# samd21_actuatorhub_Lite_TQFP32_1_0_feb20.net
KiCad netlist of a schematic drawn in EAGLE
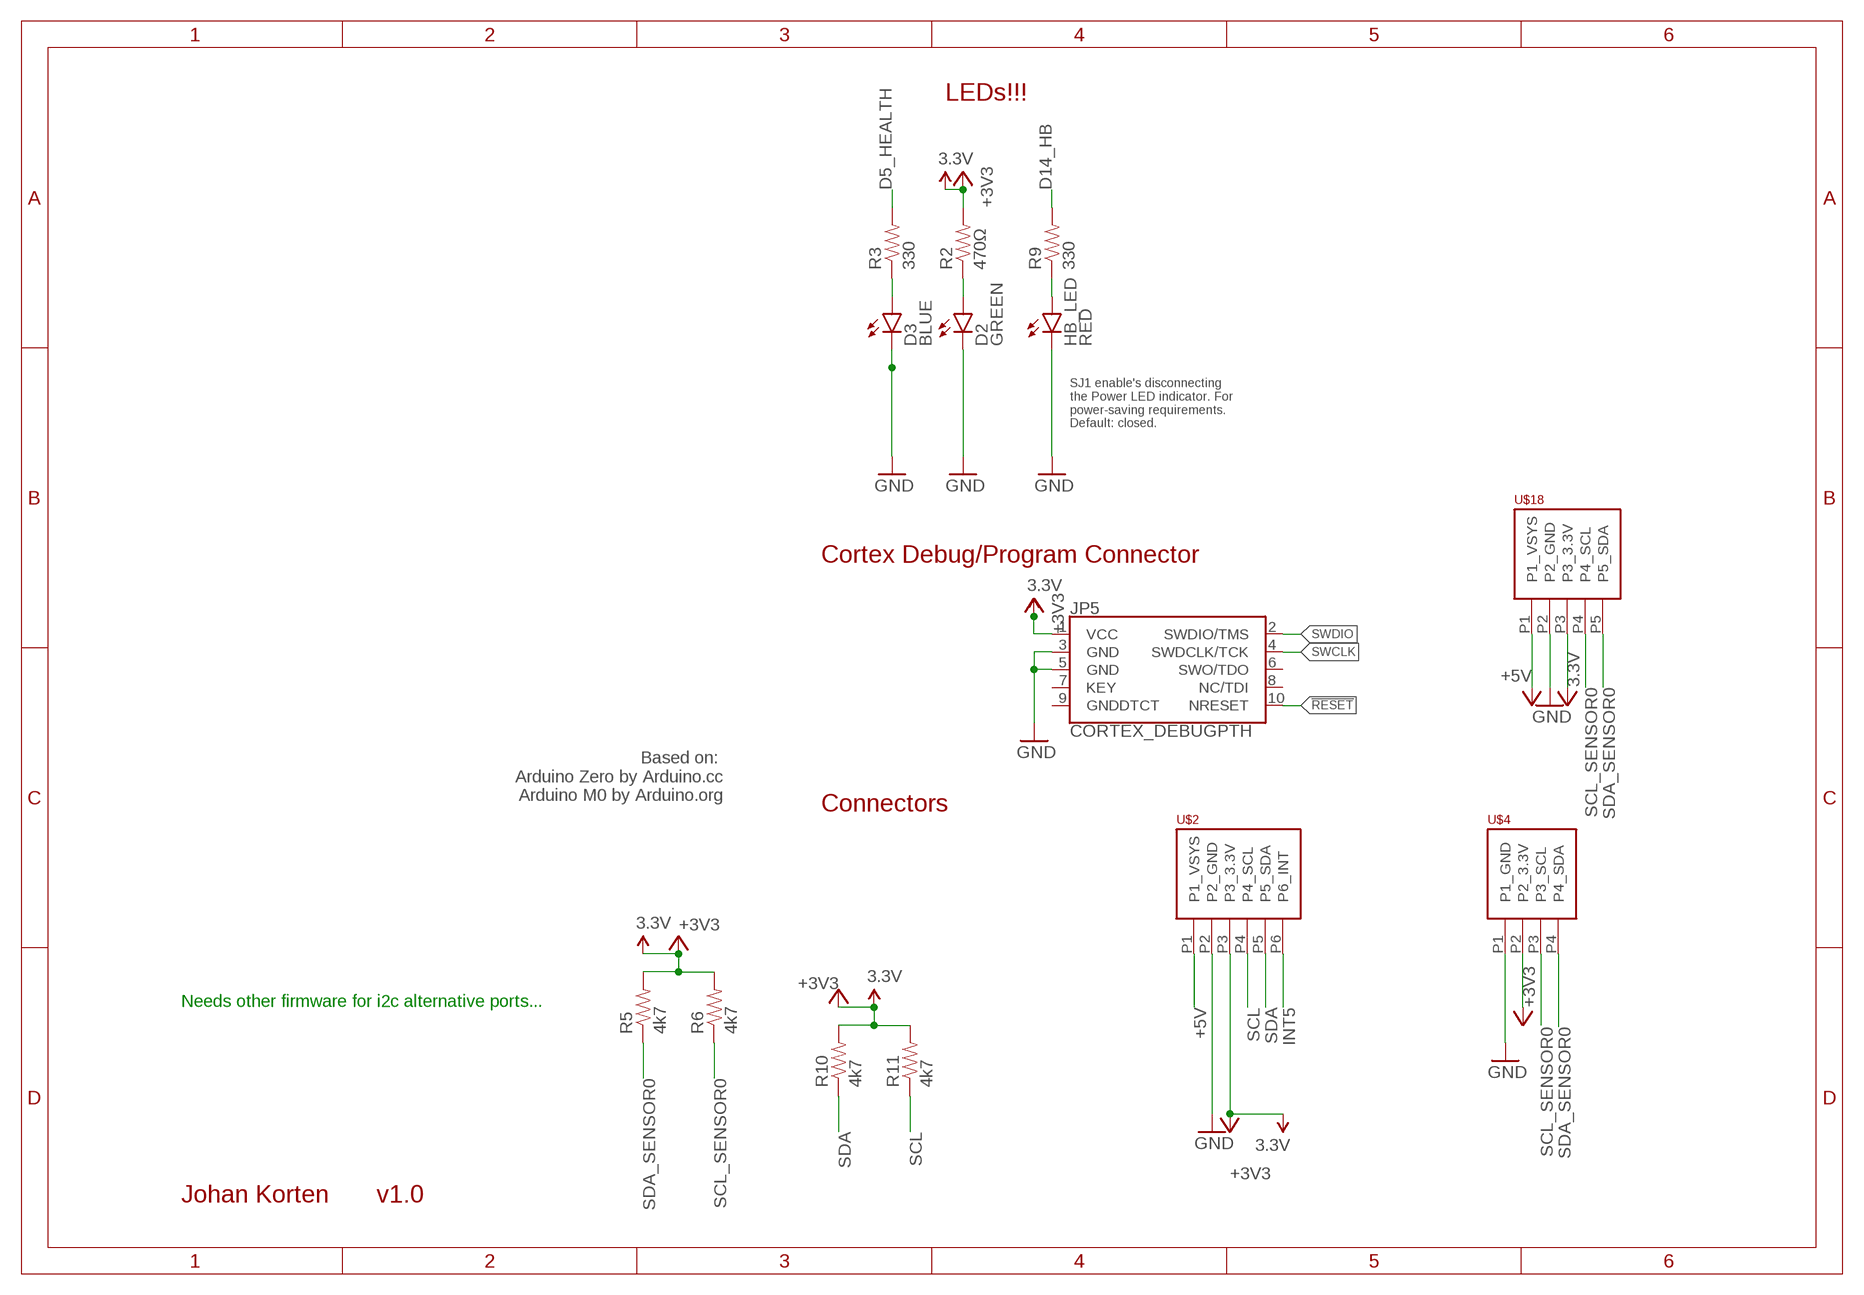
[diagram p0: schematic, sheet 1]
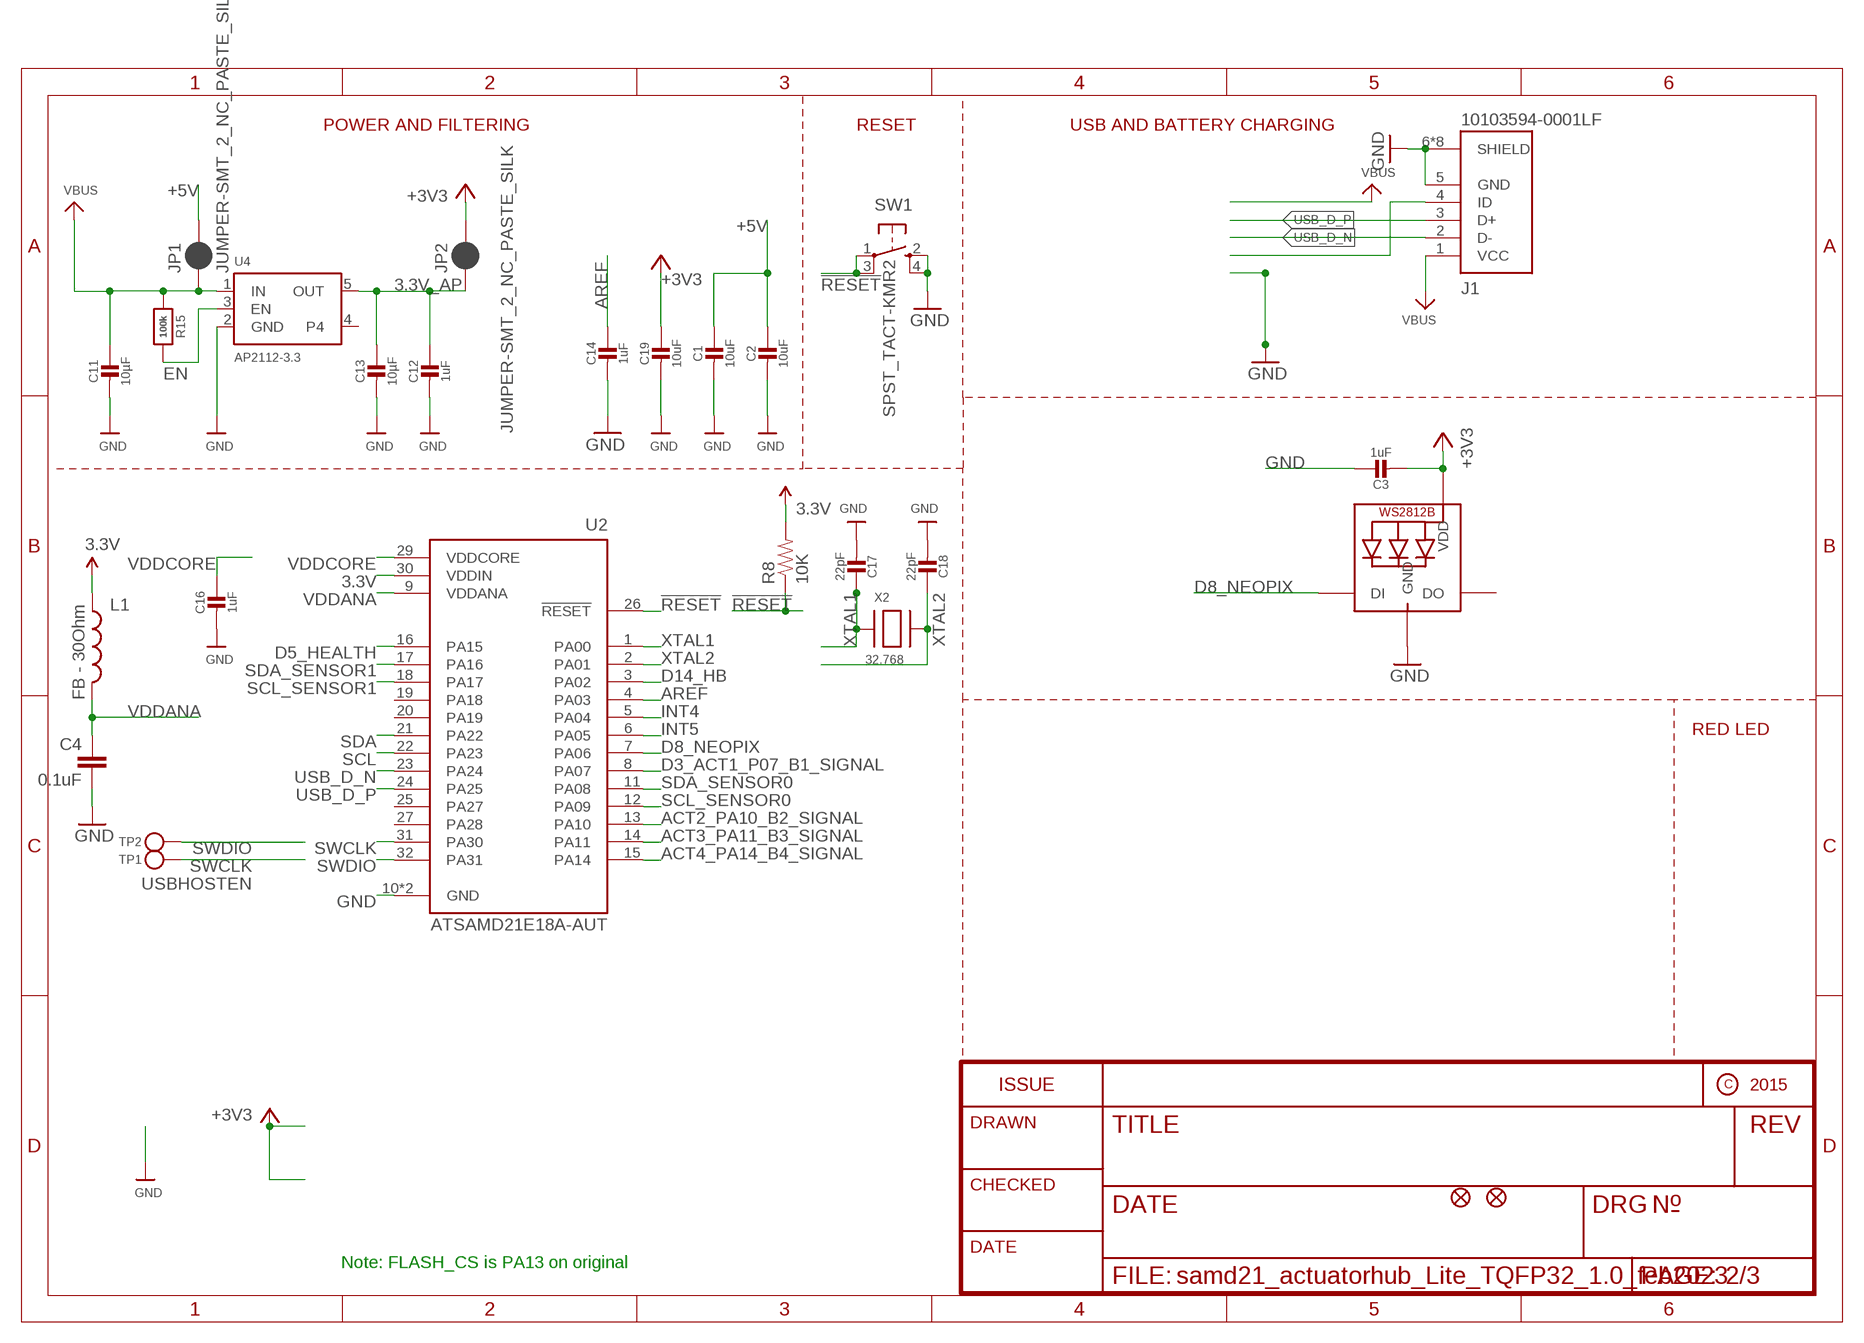
[diagram p1: schematic, sheet 2]
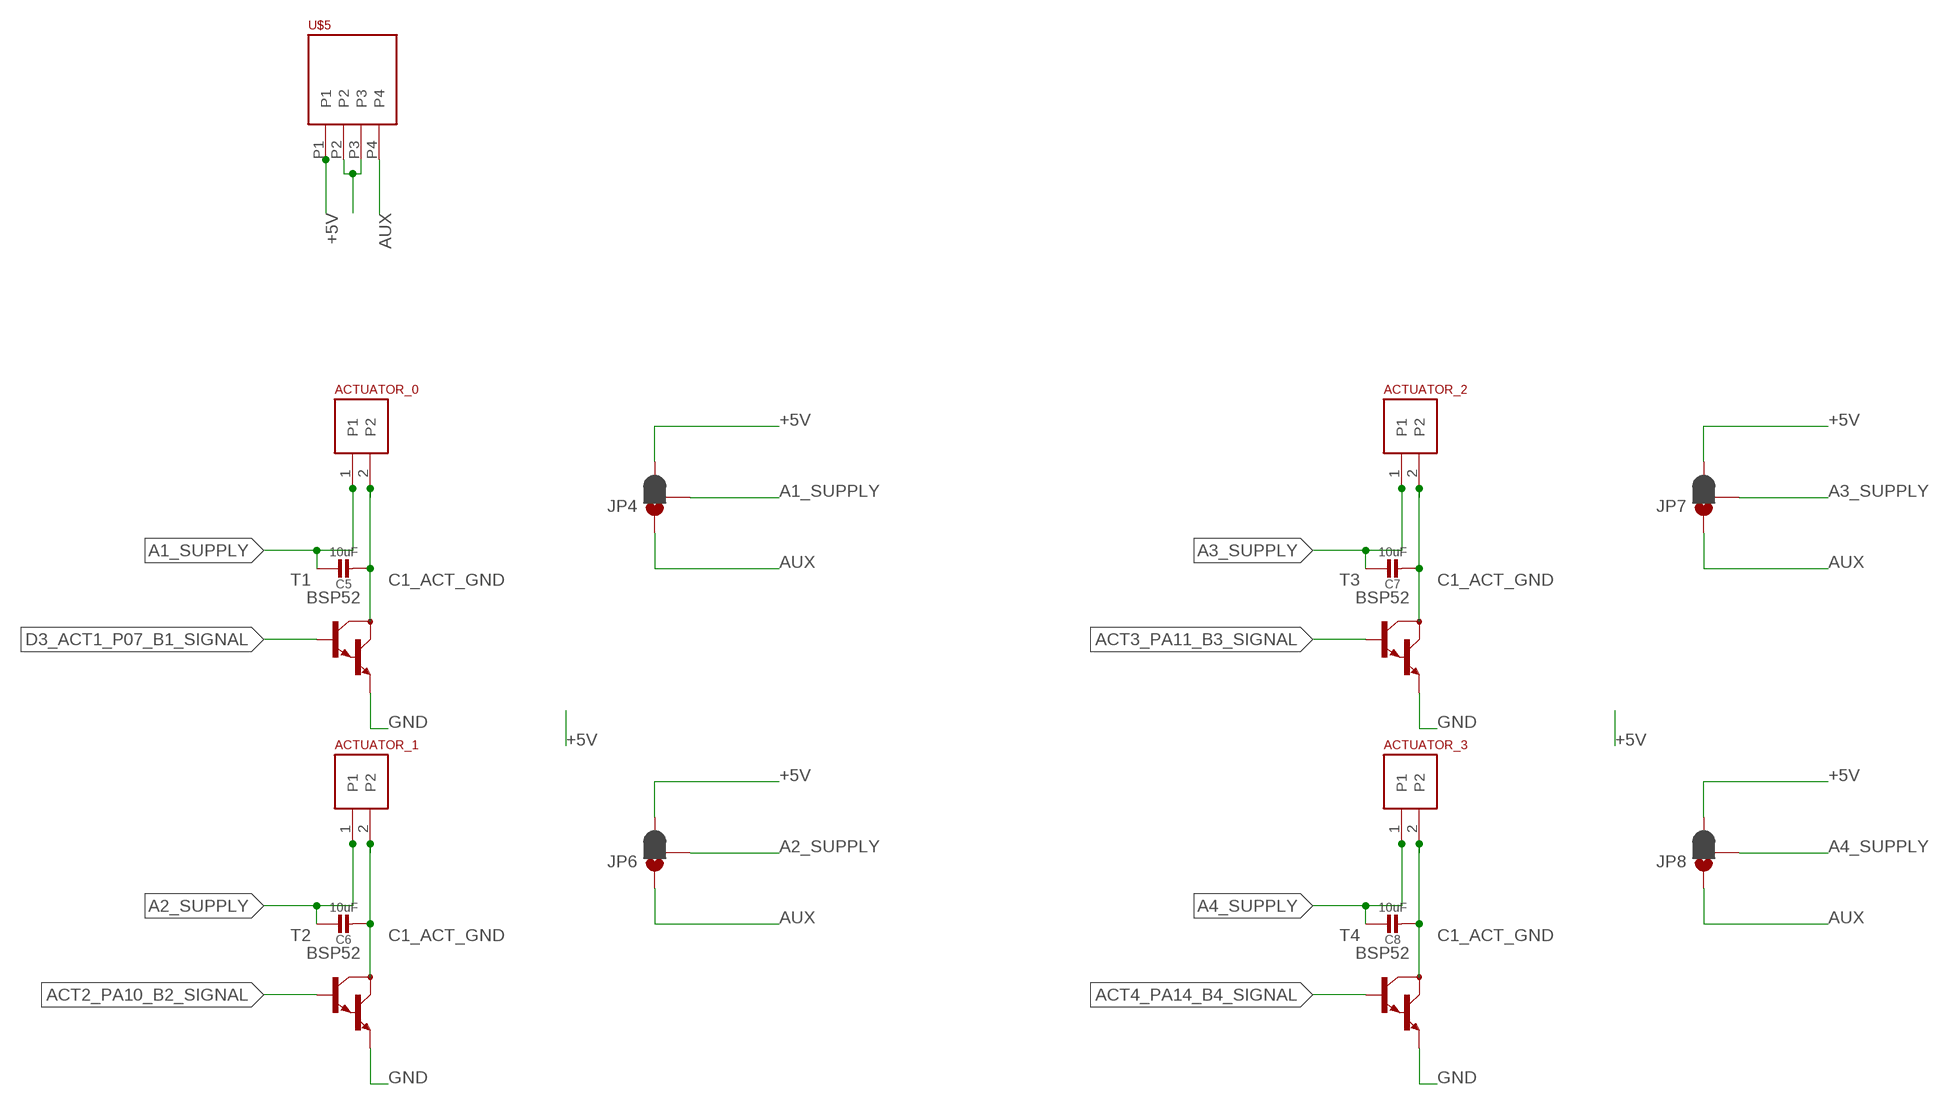
[diagram p2: schematic, sheet 3]

(export (version "E")
  (design (tool "Eeschema 10.0.6"))
  (components
    (comp (ref "C1")
      (value "10uF")
      (footprint "eagle-import:0805-NO")
      (libsource (lib "eagle-import") (part "CAP_CERAMIC0805-NOOUTLINE"))
    )
    (comp (ref "C2")
      (value "10uF")
      (footprint "eagle-import:0805-NO")
      (libsource (lib "eagle-import") (part "CAP_CERAMIC0805-NOOUTLINE"))
    )
    (comp (ref "C3")
      (value "1uF")
      (footprint "eagle-import:0603-NO")
      (libsource (lib "eagle-import") (part "CAP_CERAMIC0603_NO"))
    )
    (comp (ref "C4")
      (value "0.1uF")
      (footprint "eagle-import:0402-CAP")
      (libsource (lib "eagle-import") (part "0.1UF-16V(+-10%)(0402)"))
    )
    (comp (ref "C11")
      (value "10µF")
      (footprint "eagle-import:0805-NO")
      (libsource (lib "eagle-import") (part "CAP_CERAMIC0805-NOOUTLINE"))
    )
    (comp (ref "C12")
      (value "1uF")
      (footprint "eagle-import:0603-NO")
      (libsource (lib "eagle-import") (part "CAP_CERAMIC0603_NO"))
    )
    (comp (ref "C13")
      (value "10µF")
      (footprint "eagle-import:0805-NO")
      (libsource (lib "eagle-import") (part "CAP_CERAMIC0805-NOOUTLINE"))
    )
    (comp (ref "C14")
      (value "1uF")
      (footprint "eagle-import:0603-NO")
      (libsource (lib "eagle-import") (part "CAP_CERAMIC0603_NO"))
    )
    (comp (ref "C16")
      (value "1uF")
      (footprint "eagle-import:0603-NO")
      (libsource (lib "eagle-import") (part "CAP_CERAMIC0603_NO"))
    )
    (comp (ref "C17")
      (value "22pF")
      (footprint "eagle-import:0603-NO")
      (libsource (lib "eagle-import") (part "CAP_CERAMIC0603_NO"))
    )
    (comp (ref "C18")
      (value "22pF")
      (footprint "eagle-import:0603-NO")
      (libsource (lib "eagle-import") (part "CAP_CERAMIC0603_NO"))
    )
    (comp (ref "C19")
      (value "10uF")
      (footprint "eagle-import:0805-NO")
      (libsource (lib "eagle-import") (part "CAP_CERAMIC0805-NOOUTLINE"))
    )
    (comp (ref "J1")
      (value "10103594-0001LF")
      (footprint "eagle-import:AMPHENOL_10103594-0001LF")
      (fields (field (name "MF") "AMPHENOL ICC / FCI"))
      (libsource (lib "eagle-import") (part "10103594-0001LF"))
    )
    (comp (ref "JP1")
      (value "JUMPER-SMT_2_NC_PASTE_SILK")
      (footprint "eagle-import:SMT-JUMPER_2_NC_PASTE_SILK")
      (libsource (lib "eagle-import") (part "JUMPER-SMT_2_NC_PASTE_SILK"))
    )
    (comp (ref "JP2")
      (value "JUMPER-SMT_2_NC_PASTE_SILK")
      (footprint "eagle-import:SMT-JUMPER_2_NC_PASTE_SILK")
      (libsource (lib "eagle-import") (part "JUMPER-SMT_2_NC_PASTE_SILK"))
    )
    (comp (ref "L1")
      (value "FB - 30Ohm")
      (footprint "eagle-import:0603")
      (libsource (lib "eagle-import") (part "INDUCTOR0603"))
    )
    (comp (ref "LED1")
      (value "WS2812B3535")
      (footprint "eagle-import:LED3535")
      (libsource (lib "eagle-import") (part "WS2812B3535"))
    )
    (comp (ref "R8")
      (value "10K")
      (footprint "eagle-import:0603-RES")
      (libsource (lib "eagle-import") (part "10KOHM-1/10W-1%(0603)0603"))
    )
    (comp (ref "R15")
      (value "100k")
      (footprint "eagle-import:0603-NO")
      (libsource (lib "eagle-import") (part "RESISTOR_0603_NOOUT"))
    )
    (comp (ref "SW1")
      (value "SPST_TACT-KMR2")
      (footprint "eagle-import:KMR2")
      (libsource (lib "eagle-import") (part "SPST_TACT-KMR2"))
    )
    (comp (ref "TP1")
      (value "TESTPOINTROUND1.5MM")
      (footprint "eagle-import:TESTPOINT_ROUND_1.5MM")
      (libsource (lib "eagle-import") (part "TESTPOINTROUND1.5MM"))
    )
    (comp (ref "TP2")
      (value "TESTPOINTROUND1.5MM")
      (footprint "eagle-import:TESTPOINT_ROUND_1.5MM")
      (libsource (lib "eagle-import") (part "TESTPOINTROUND1.5MM"))
    )
    (comp (ref "U$34")
      (value "FIDUCIAL\"\"")
      (footprint "eagle-import:FIDUCIAL_1MM")
      (libsource (lib "eagle-import") (part "FIDUCIAL{dblquote}{dblquote}"))
    )
    (comp (ref "U$35")
      (value "FIDUCIAL\"\"")
      (footprint "eagle-import:FIDUCIAL_1MM")
      (libsource (lib "eagle-import") (part "FIDUCIAL{dblquote}{dblquote}"))
    )
    (comp (ref "U2")
      (value "ATSAMD21E18A-AUT")
      (footprint "eagle-import:QFP80P900X900X120-32N")
      (fields (field (name "MF") "Microchip") (field (name "MP") "ATSAMD21E18A-AU"))
      (libsource (lib "eagle-import") (part "ATSAMD21E18A-AUT"))
    )
    (comp (ref "U4")
      (value "AP2112-3.3")
      (footprint "eagle-import:SOT23-5")
      (libsource (lib "eagle-import") (part "VREG_SOT23-5"))
    )
    (comp (ref "X2")
      (value "32.768")
      (footprint "eagle-import:XTAL3215")
      (libsource (lib "eagle-import") (part "XTAL-3.2X1.5"))
    )
    (comp (ref "ACTUATOR_0")
      (value "PHOENIX_PTSM_M2TH")
      (footprint "eagle-import:PTSM_M2_THRHOLE")
      (libsource (lib "eagle-import") (part "PHOENIX_PTSM_M2TH"))
    )
    (comp (ref "ACTUATOR_1")
      (value "PHOENIX_PTSM_M2TH")
      (footprint "eagle-import:PTSM_M2_THRHOLE")
      (libsource (lib "eagle-import") (part "PHOENIX_PTSM_M2TH"))
    )
    (comp (ref "ACTUATOR_2")
      (value "PHOENIX_PTSM_M2TH")
      (footprint "eagle-import:PTSM_M2_THRHOLE")
      (libsource (lib "eagle-import") (part "PHOENIX_PTSM_M2TH"))
    )
    (comp (ref "ACTUATOR_3")
      (value "PHOENIX_PTSM_M2TH")
      (footprint "eagle-import:PTSM_M2_THRHOLE")
      (libsource (lib "eagle-import") (part "PHOENIX_PTSM_M2TH"))
    )
    (comp (ref "C5")
      (value "10uF")
      (footprint "eagle-import:0805-NO")
      (libsource (lib "eagle-import") (part "CAP_CERAMIC0805-NOOUTLINE"))
    )
    (comp (ref "C6")
      (value "10uF")
      (footprint "eagle-import:0805-NO")
      (libsource (lib "eagle-import") (part "CAP_CERAMIC0805-NOOUTLINE"))
    )
    (comp (ref "C7")
      (value "10uF")
      (footprint "eagle-import:0805-NO")
      (libsource (lib "eagle-import") (part "CAP_CERAMIC0805-NOOUTLINE"))
    )
    (comp (ref "C8")
      (value "10uF")
      (footprint "eagle-import:0805-NO")
      (libsource (lib "eagle-import") (part "CAP_CERAMIC0805-NOOUTLINE"))
    )
    (comp (ref "JP4")
      (value "JUMPER-SMT_3_1-NC_PASTE_SILK")
      (footprint "eagle-import:SMT-JUMPER_3_1-NC_PASTE_SILK")
      (libsource (lib "eagle-import") (part "JUMPER-SMT_3_1-NC_PASTE_SILK"))
    )
    (comp (ref "JP6")
      (value "JUMPER-SMT_3_1-NC_PASTE_SILK")
      (footprint "eagle-import:SMT-JUMPER_3_1-NC_PASTE_SILK")
      (libsource (lib "eagle-import") (part "JUMPER-SMT_3_1-NC_PASTE_SILK"))
    )
    (comp (ref "JP7")
      (value "JUMPER-SMT_3_1-NC_PASTE_SILK")
      (footprint "eagle-import:SMT-JUMPER_3_1-NC_PASTE_SILK")
      (libsource (lib "eagle-import") (part "JUMPER-SMT_3_1-NC_PASTE_SILK"))
    )
    (comp (ref "JP8")
      (value "JUMPER-SMT_3_1-NC_PASTE_SILK")
      (footprint "eagle-import:SMT-JUMPER_3_1-NC_PASTE_SILK")
      (libsource (lib "eagle-import") (part "JUMPER-SMT_3_1-NC_PASTE_SILK"))
    )
    (comp (ref "T1")
      (value "BSP52")
      (footprint "eagle-import:SOT-223-4")
      (fields (field (name "MF") "ON Semiconductor"))
      (libsource (lib "eagle-import") (part "BSP52"))
    )
    (comp (ref "T2")
      (value "BSP52")
      (footprint "eagle-import:SOT-223-4")
      (fields (field (name "MF") "ON Semiconductor"))
      (libsource (lib "eagle-import") (part "BSP52"))
    )
    (comp (ref "T3")
      (value "BSP52")
      (footprint "eagle-import:SOT-223-4")
      (fields (field (name "MF") "ON Semiconductor"))
      (libsource (lib "eagle-import") (part "BSP52"))
    )
    (comp (ref "T4")
      (value "BSP52")
      (footprint "eagle-import:SOT-223-4")
      (fields (field (name "MF") "ON Semiconductor"))
      (libsource (lib "eagle-import") (part "BSP52"))
    )
    (comp (ref "U$5")
      (value "PHOENIX_PTSM_M4_TH_ANGLE")
      (footprint "eagle-import:PTSM_M4_TH_ANGLE_NEUTRAL")
      (libsource (lib "eagle-import") (part "PHOENIX_PTSM_M4_TH_ANGLE"))
    )
    (comp (ref "D2")
      (value "GREEN")
      (footprint "eagle-import:LED-0603")
      (libsource (lib "eagle-import") (part "LED-RED0603"))
    )
    (comp (ref "D3")
      (value "BLUE")
      (footprint "eagle-import:LED-0603")
      (libsource (lib "eagle-import") (part "LED-BLUE0603"))
    )
    (comp (ref "HB_LED")
      (value "RED")
      (footprint "eagle-import:LED-0603")
      (libsource (lib "eagle-import") (part "LED-RED0603"))
    )
    (comp (ref "JP5")
      (value "CORTEX_DEBUGPTH")
      (footprint "eagle-import:2X5-PTH-1.27MM")
      (libsource (lib "eagle-import") (part "CORTEX_DEBUGPTH"))
    )
    (comp (ref "R2")
      (value "470Ω")
      (footprint "eagle-import:0603-RES")
      (libsource (lib "eagle-import") (part "330OHM1/10W1%(0603)"))
    )
    (comp (ref "R3")
      (value "330")
      (footprint "eagle-import:0603-RES")
      (libsource (lib "eagle-import") (part "330OHM1/10W1%(0603)"))
    )
    (comp (ref "R5")
      (value "4k7")
      (footprint "eagle-import:0603-RES")
      (libsource (lib "eagle-import") (part "330OHM1/10W1%(0603)"))
    )
    (comp (ref "R6")
      (value "4k7")
      (footprint "eagle-import:0603-RES")
      (libsource (lib "eagle-import") (part "330OHM1/10W1%(0603)"))
    )
    (comp (ref "R9")
      (value "330")
      (footprint "eagle-import:0603-RES")
      (libsource (lib "eagle-import") (part "330OHM1/10W1%(0603)"))
    )
    (comp (ref "R10")
      (value "4k7")
      (footprint "eagle-import:0603-RES")
      (libsource (lib "eagle-import") (part "330OHM1/10W1%(0603)"))
    )
    (comp (ref "R11")
      (value "4k7")
      (footprint "eagle-import:0603-RES")
      (libsource (lib "eagle-import") (part "330OHM1/10W1%(0603)"))
    )
    (comp (ref "U$2")
      (value "PHOENIX_PTSM_M6_TH_I2CPPANGLE")
      (footprint "eagle-import:PTSM_M6_THRHOLE")
      (libsource (lib "eagle-import") (part "PHOENIX_PTSM_M6_TH_I2CPPANGLE"))
    )
    (comp (ref "U$4")
      (value "PHOENIX_PTSM_M4_THANGLE")
      (footprint "eagle-import:PTSM_M4_TH")
      (libsource (lib "eagle-import") (part "PHOENIX_PTSM_M4_THANGLE"))
    )
    (comp (ref "U$18")
      (value "PHOENIX_PTSM_M5_TH_I2C++")
      (footprint "eagle-import:PTSM_M5_THRHOLE")
      (libsource (lib "eagle-import") (part "PHOENIX_PTSM_M5_TH_I2C++"))
    )
  )
  (nets
    (net (code "1") (name "+5V") (class "Default")
      (node (ref "C1") (pin "1") (pinfunction "1_1") (pintype "passive"))
      (node (ref "C2") (pin "1") (pinfunction "1_1") (pintype "passive"))
      (node (ref "JP1") (pin "2") (pinfunction "2_2") (pintype "passive"))
      (node (ref "JP4") (pin "3") (pinfunction "3_3") (pintype "passive"))
      (node (ref "JP6") (pin "3") (pinfunction "3_3") (pintype "passive"))
      (node (ref "JP7") (pin "3") (pinfunction "3_3") (pintype "passive"))
      (node (ref "JP8") (pin "3") (pinfunction "3_3") (pintype "passive"))
      (node (ref "U$18") (pin "P1") (pinfunction "P1_VSYS_P1") (pintype "power_in"))
      (node (ref "U$2") (pin "P1") (pinfunction "P1_VSYS_P1") (pintype "power_in"))
      (node (ref "U$5") (pin "P1") (pinfunction "P1_P1") (pintype "power_in"))
    )
    (net (code "2") (name "3.3V") (class "Default")
      (node (ref "C19") (pin "1") (pinfunction "1_1") (pintype "passive"))
      (node (ref "C3") (pin "2") (pinfunction "2_2") (pintype "passive"))
      (node (ref "JP2") (pin "2") (pinfunction "2_2") (pintype "passive"))
      (node (ref "JP5") (pin "1") (pinfunction "VCC_1") (pintype "bidirectional"))
      (node (ref "L1") (pin "1") (pinfunction "1_1") (pintype "passive"))
      (node (ref "LED1") (pin "2") (pinfunction "VDD_2") (pintype "power_in"))
      (node (ref "R10") (pin "2") (pinfunction "2_2") (pintype "passive"))
      (node (ref "R11") (pin "2") (pinfunction "2_2") (pintype "passive"))
      (node (ref "R2") (pin "2") (pinfunction "2_2") (pintype "passive"))
      (node (ref "R5") (pin "2") (pinfunction "2_2") (pintype "passive"))
      (node (ref "R6") (pin "2") (pinfunction "2_2") (pintype "passive"))
      (node (ref "R8") (pin "2") (pinfunction "2_2") (pintype "passive"))
      (node (ref "U$18") (pin "P3") (pinfunction "P3_3.3V_P3") (pintype "power_in"))
      (node (ref "U$2") (pin "P3") (pinfunction "P3_3.3V_P3") (pintype "power_in"))
      (node (ref "U$4") (pin "P2") (pinfunction "P2_3.3V_P2") (pintype "power_in"))
      (node (ref "U2") (pin "30") (pinfunction "VDDIN_30") (pintype "power_in"))
    )
    (net (code "3") (name "3.3V_AP") (class "Default")
      (node (ref "C12") (pin "1") (pinfunction "1_1") (pintype "passive"))
      (node (ref "C13") (pin "1") (pinfunction "1_1") (pintype "passive"))
      (node (ref "JP2") (pin "1") (pinfunction "1_1") (pintype "passive"))
      (node (ref "U4") (pin "5") (pinfunction "OUT_5") (pintype "power_in"))
    )
    (net (code "4") (name "A1_SUPPLY") (class "Default")
      (node (ref "ACTUATOR_0") (pin "1") (pinfunction "P1_1") (pintype "bidirectional"))
      (node (ref "C5") (pin "1") (pinfunction "1_1") (pintype "passive"))
      (node (ref "JP4") (pin "2") (pinfunction "2_2") (pintype "passive"))
    )
    (net (code "5") (name "A2_SUPPLY") (class "Default")
      (node (ref "ACTUATOR_1") (pin "1") (pinfunction "P1_1") (pintype "bidirectional"))
      (node (ref "C6") (pin "1") (pinfunction "1_1") (pintype "passive"))
      (node (ref "JP6") (pin "2") (pinfunction "2_2") (pintype "passive"))
    )
    (net (code "6") (name "A3_SUPPLY") (class "Default")
      (node (ref "ACTUATOR_2") (pin "1") (pinfunction "P1_1") (pintype "bidirectional"))
      (node (ref "C7") (pin "1") (pinfunction "1_1") (pintype "passive"))
      (node (ref "JP7") (pin "2") (pinfunction "2_2") (pintype "passive"))
    )
    (net (code "7") (name "A4_SUPPLY") (class "Default")
      (node (ref "ACTUATOR_3") (pin "1") (pinfunction "P1_1") (pintype "bidirectional"))
      (node (ref "C8") (pin "1") (pinfunction "1_1") (pintype "passive"))
      (node (ref "JP8") (pin "2") (pinfunction "2_2") (pintype "passive"))
    )
    (net (code "8") (name "ACT2_PA10_B2_SIGNAL") (class "Default")
      (node (ref "T2") (pin "1") (pinfunction "B_1") (pintype "passive"))
      (node (ref "U2") (pin "13") (pinfunction "PA10_13") (pintype "bidirectional"))
    )
    (net (code "9") (name "ACT3_PA11_B3_SIGNAL") (class "Default")
      (node (ref "T3") (pin "1") (pinfunction "B_1") (pintype "passive"))
      (node (ref "U2") (pin "14") (pinfunction "PA11_14") (pintype "bidirectional"))
    )
    (net (code "10") (name "ACT4_PA14_B4_SIGNAL") (class "Default")
      (node (ref "T4") (pin "1") (pinfunction "B_1") (pintype "passive"))
      (node (ref "U2") (pin "15") (pinfunction "PA14_15") (pintype "bidirectional"))
    )
    (net (code "11") (name "AREF") (class "Default")
      (node (ref "C14") (pin "1") (pinfunction "1_1") (pintype "passive"))
      (node (ref "U2") (pin "4") (pinfunction "PA03_4") (pintype "bidirectional"))
    )
    (net (code "12") (name "AUX") (class "Default")
      (node (ref "JP4") (pin "1") (pinfunction "1_1") (pintype "passive"))
      (node (ref "JP6") (pin "1") (pinfunction "1_1") (pintype "passive"))
      (node (ref "JP7") (pin "1") (pinfunction "1_1") (pintype "passive"))
      (node (ref "JP8") (pin "1") (pinfunction "1_1") (pintype "passive"))
      (node (ref "U$5") (pin "P4") (pinfunction "P4_P4") (pintype "power_in"))
    )
    (net (code "13") (name "C1_ACT_GND") (class "Default")
      (node (ref "ACTUATOR_0") (pin "2") (pinfunction "P2_2") (pintype "bidirectional"))
      (node (ref "ACTUATOR_1") (pin "2") (pinfunction "P2_2") (pintype "bidirectional"))
      (node (ref "ACTUATOR_2") (pin "2") (pinfunction "P2_2") (pintype "bidirectional"))
      (node (ref "ACTUATOR_3") (pin "2") (pinfunction "P2_2") (pintype "bidirectional"))
      (node (ref "C5") (pin "2") (pinfunction "2_2") (pintype "passive"))
      (node (ref "C6") (pin "2") (pinfunction "2_2") (pintype "passive"))
      (node (ref "C7") (pin "2") (pinfunction "2_2") (pintype "passive"))
      (node (ref "C8") (pin "2") (pinfunction "2_2") (pintype "passive"))
      (node (ref "T1") (pin "2") (pinfunction "C_2") (pintype "passive"))
      (node (ref "T1") (pin "4") (pinfunction "C_4") (pintype "passive"))
      (node (ref "T2") (pin "2") (pinfunction "C_2") (pintype "passive"))
      (node (ref "T2") (pin "4") (pinfunction "C_4") (pintype "passive"))
      (node (ref "T3") (pin "2") (pinfunction "C_2") (pintype "passive"))
      (node (ref "T3") (pin "4") (pinfunction "C_4") (pintype "passive"))
      (node (ref "T4") (pin "2") (pinfunction "C_2") (pintype "passive"))
      (node (ref "T4") (pin "4") (pinfunction "C_4") (pintype "passive"))
    )
    (net (code "14") (name "D3_ACT1_P07_B1_SIGNAL") (class "Default")
      (node (ref "T1") (pin "1") (pinfunction "B_1") (pintype "passive"))
      (node (ref "U2") (pin "8") (pinfunction "PA07_8") (pintype "bidirectional"))
    )
    (net (code "15") (name "D5_HEALTH") (class "Default")
      (node (ref "R3") (pin "2") (pinfunction "2_2") (pintype "passive"))
      (node (ref "U2") (pin "16") (pinfunction "PA15_16") (pintype "bidirectional"))
    )
    (net (code "16") (name "D8_NEOPIX") (class "Default")
      (node (ref "LED1") (pin "1") (pinfunction "DI_1") (pintype "input"))
      (node (ref "U2") (pin "7") (pinfunction "PA06_7") (pintype "bidirectional"))
    )
    (net (code "17") (name "D14_HB") (class "Default")
      (node (ref "R9") (pin "2") (pinfunction "2_2") (pintype "passive"))
      (node (ref "U2") (pin "3") (pinfunction "PA02_3") (pintype "bidirectional"))
    )
    (net (code "18") (name "EN") (class "Default")
      (node (ref "R15") (pin "2") (pinfunction "2_2") (pintype "passive"))
      (node (ref "U4") (pin "3") (pinfunction "EN_3") (pintype "input"))
    )
    (net (code "19") (name "GND") (class "Default")
      (node (ref "C1") (pin "2") (pinfunction "2_2") (pintype "passive"))
      (node (ref "C11") (pin "2") (pinfunction "2_2") (pintype "passive"))
      (node (ref "C12") (pin "2") (pinfunction "2_2") (pintype "passive"))
      (node (ref "C13") (pin "2") (pinfunction "2_2") (pintype "passive"))
      (node (ref "C14") (pin "2") (pinfunction "2_2") (pintype "passive"))
      (node (ref "C16") (pin "2") (pinfunction "2_2") (pintype "passive"))
      (node (ref "C17") (pin "2") (pinfunction "2_2") (pintype "passive"))
      (node (ref "C18") (pin "2") (pinfunction "2_2") (pintype "passive"))
      (node (ref "C19") (pin "2") (pinfunction "2_2") (pintype "passive"))
      (node (ref "C2") (pin "2") (pinfunction "2_2") (pintype "passive"))
      (node (ref "C3") (pin "1") (pinfunction "1_1") (pintype "passive"))
      (node (ref "C4") (pin "2") (pinfunction "2_2") (pintype "passive"))
      (node (ref "D2") (pin "C") (pinfunction "C_C") (pintype "passive"))
      (node (ref "D3") (pin "C") (pinfunction "C_C") (pintype "passive"))
      (node (ref "HB_LED") (pin "C") (pinfunction "C_C") (pintype "passive"))
      (node (ref "J1") (pin "10") (pinfunction "SHIELD_10") (pintype "passive"))
      (node (ref "J1") (pin "11") (pinfunction "SHIELD_11") (pintype "passive"))
      (node (ref "J1") (pin "5") (pinfunction "GND_5") (pintype "power_in"))
      (node (ref "J1") (pin "6") (pinfunction "SHIELD_6") (pintype "passive"))
      (node (ref "J1") (pin "7") (pinfunction "SHIELD_7") (pintype "passive"))
      (node (ref "J1") (pin "8") (pinfunction "SHIELD_8") (pintype "passive"))
      (node (ref "J1") (pin "9") (pinfunction "SHIELD_9") (pintype "passive"))
      (node (ref "J1") (pin "S1") (pinfunction "SHIELD_S1") (pintype "passive"))
      (node (ref "J1") (pin "S2") (pinfunction "SHIELD_S2") (pintype "passive"))
      (node (ref "JP5") (pin "3") (pinfunction "GND_3") (pintype "bidirectional"))
      (node (ref "JP5") (pin "5") (pinfunction "GND_5") (pintype "bidirectional"))
      (node (ref "LED1") (pin "4") (pinfunction "GND_4") (pintype "power_in"))
      (node (ref "SW1") (pin "2") (pinfunction "S_2") (pintype "passive"))
      (node (ref "SW1") (pin "4") (pinfunction "S1_4") (pintype "passive"))
      (node (ref "T1") (pin "3") (pinfunction "E_3") (pintype "passive"))
      (node (ref "T2") (pin "3") (pinfunction "E_3") (pintype "passive"))
      (node (ref "T3") (pin "3") (pinfunction "E_3") (pintype "passive"))
      (node (ref "T4") (pin "3") (pinfunction "E_3") (pintype "passive"))
      (node (ref "U$18") (pin "P2") (pinfunction "P2_GND_P2") (pintype "power_in"))
      (node (ref "U$2") (pin "P2") (pinfunction "P2_GND_P2") (pintype "power_in"))
      (node (ref "U$4") (pin "P1") (pinfunction "P1_GND_P1") (pintype "power_in"))
      (node (ref "U2") (pin "10") (pinfunction "GND_10") (pintype "power_in"))
      (node (ref "U2") (pin "28") (pinfunction "GND_28") (pintype "power_in"))
      (node (ref "U4") (pin "2") (pinfunction "GND_2") (pintype "power_in"))
    )
    (net (code "20") (name "INT4") (class "Default")
      (node (ref "U2") (pin "5") (pinfunction "PA04_5") (pintype "bidirectional"))
    )
    (net (code "21") (name "INT5") (class "Default")
      (node (ref "U$2") (pin "P6") (pinfunction "P6_INT_P6") (pintype "power_in"))
      (node (ref "U2") (pin "6") (pinfunction "PA05_6") (pintype "bidirectional"))
    )
    (net (code "22") (name "Net-(D2-PadA)") (class "Default")
      (node (ref "D2") (pin "A") (pinfunction "A_A") (pintype "passive"))
      (node (ref "R2") (pin "1") (pinfunction "1_1") (pintype "passive"))
    )
    (net (code "23") (name "Net-(D3-PadA)") (class "Default")
      (node (ref "D3") (pin "A") (pinfunction "A_A") (pintype "passive"))
      (node (ref "R3") (pin "1") (pinfunction "1_1") (pintype "passive"))
    )
    (net (code "24") (name "Net-(HB_LED-PadA)") (class "Default")
      (node (ref "HB_LED") (pin "A") (pinfunction "A_A") (pintype "passive"))
      (node (ref "R9") (pin "1") (pinfunction "1_1") (pintype "passive"))
    )
    (net (code "25") (name "Net-(U$5-PadP2)") (class "Default")
      (node (ref "U$5") (pin "P2") (pinfunction "P2_P2") (pintype "power_in"))
      (node (ref "U$5") (pin "P3") (pinfunction "P3_P3") (pintype "power_in"))
    )
    (net (code "26") (name "SCL") (class "Default")
      (node (ref "R11") (pin "1") (pinfunction "1_1") (pintype "passive"))
      (node (ref "U$2") (pin "P4") (pinfunction "P4_SCL_P4") (pintype "bidirectional"))
      (node (ref "U2") (pin "22") (pinfunction "PA23_22") (pintype "bidirectional"))
    )
    (net (code "27") (name "SCL_SENSOR0") (class "Default")
      (node (ref "R6") (pin "1") (pinfunction "1_1") (pintype "passive"))
      (node (ref "U$18") (pin "P4") (pinfunction "P4_SCL_P4") (pintype "bidirectional"))
      (node (ref "U$4") (pin "P3") (pinfunction "P3_SCL_P3") (pintype "bidirectional"))
      (node (ref "U2") (pin "12") (pinfunction "PA09_12") (pintype "bidirectional"))
    )
    (net (code "28") (name "SCL_SENSOR1") (class "Default")
      (node (ref "U2") (pin "18") (pinfunction "PA17_18") (pintype "bidirectional"))
    )
    (net (code "29") (name "SDA") (class "Default")
      (node (ref "R10") (pin "1") (pinfunction "1_1") (pintype "passive"))
      (node (ref "U$2") (pin "P5") (pinfunction "P5_SDA_P5") (pintype "bidirectional"))
      (node (ref "U2") (pin "21") (pinfunction "PA22_21") (pintype "bidirectional"))
    )
    (net (code "30") (name "SDA_SENSOR0") (class "Default")
      (node (ref "R5") (pin "1") (pinfunction "1_1") (pintype "passive"))
      (node (ref "U$18") (pin "P5") (pinfunction "P5_SDA_P5") (pintype "bidirectional"))
      (node (ref "U$4") (pin "P4") (pinfunction "P4_SDA_P4") (pintype "bidirectional"))
      (node (ref "U2") (pin "11") (pinfunction "PA08_11") (pintype "bidirectional"))
    )
    (net (code "31") (name "SDA_SENSOR1") (class "Default")
      (node (ref "U2") (pin "17") (pinfunction "PA16_17") (pintype "bidirectional"))
    )
    (net (code "32") (name "SWCLK") (class "Default")
      (node (ref "JP5") (pin "4") (pinfunction "SWDCLK/TCK_4") (pintype "bidirectional"))
      (node (ref "TP1") (pin "P$1") (pinfunction "P$1_P$1") (pintype "bidirectional"))
      (node (ref "U2") (pin "31") (pinfunction "PA30_31") (pintype "bidirectional"))
    )
    (net (code "33") (name "SWDIO") (class "Default")
      (node (ref "JP5") (pin "2") (pinfunction "SWDIO/TMS_2") (pintype "bidirectional"))
      (node (ref "TP2") (pin "P$1") (pinfunction "P$1_P$1") (pintype "bidirectional"))
      (node (ref "U2") (pin "32") (pinfunction "PA31_32") (pintype "bidirectional"))
    )
    (net (code "34") (name "USB_D_N") (class "Default")
      (node (ref "J1") (pin "2") (pinfunction "D-_2") (pintype "bidirectional"))
      (node (ref "U2") (pin "23") (pinfunction "PA24_23") (pintype "bidirectional"))
    )
    (net (code "35") (name "USB_D_P") (class "Default")
      (node (ref "J1") (pin "3") (pinfunction "D+_3") (pintype "bidirectional"))
      (node (ref "U2") (pin "24") (pinfunction "PA25_24") (pintype "bidirectional"))
    )
    (net (code "36") (name "VBUS") (class "Default")
      (node (ref "C11") (pin "1") (pinfunction "1_1") (pintype "passive"))
      (node (ref "J1") (pin "1") (pinfunction "VCC_1") (pintype "power_in"))
      (node (ref "JP1") (pin "1") (pinfunction "1_1") (pintype "passive"))
      (node (ref "R15") (pin "1") (pinfunction "1_1") (pintype "passive"))
      (node (ref "U4") (pin "1") (pinfunction "IN_1") (pintype "power_in"))
    )
    (net (code "37") (name "VDDANA") (class "Default")
      (node (ref "C4") (pin "1") (pinfunction "1_1") (pintype "passive"))
      (node (ref "L1") (pin "2") (pinfunction "2_2") (pintype "passive"))
      (node (ref "U2") (pin "9") (pinfunction "VDDANA_9") (pintype "power_in"))
    )
    (net (code "38") (name "VDDCORE") (class "Default")
      (node (ref "C16") (pin "1") (pinfunction "1_1") (pintype "passive"))
      (node (ref "U2") (pin "29") (pinfunction "VDDCORE_29") (pintype "power_in"))
    )
    (net (code "39") (name "XTAL1") (class "Default")
      (node (ref "C17") (pin "1") (pinfunction "1_1") (pintype "passive"))
      (node (ref "U2") (pin "1") (pinfunction "PA00_1") (pintype "bidirectional"))
      (node (ref "X2") (pin "P$1") (pinfunction "P$1_P$1") (pintype "bidirectional"))
    )
    (net (code "40") (name "XTAL2") (class "Default")
      (node (ref "C18") (pin "1") (pinfunction "1_1") (pintype "passive"))
      (node (ref "U2") (pin "2") (pinfunction "PA01_2") (pintype "bidirectional"))
      (node (ref "X2") (pin "P$2") (pinfunction "P$2_P$2") (pintype "bidirectional"))
    )
    (net (code "41") (name "unconnected-(J1-ID-Pad4)") (class "Default")
      (node (ref "J1") (pin "4") (pinfunction "ID_4") (pintype "bidirectional"))
    )
    (net (code "42") (name "unconnected-(JP5-GNDDTCT-Pad9)") (class "Default")
      (node (ref "JP5") (pin "9") (pinfunction "GNDDTCT_9") (pintype "bidirectional"))
    )
    (net (code "43") (name "unconnected-(JP5-KEY-Pad7)") (class "Default")
      (node (ref "JP5") (pin "7") (pinfunction "KEY_7") (pintype "bidirectional"))
    )
    (net (code "44") (name "unconnected-(JP5-NC{slash}TDI-Pad8)") (class "Default")
      (node (ref "JP5") (pin "8") (pinfunction "NC/TDI_8") (pintype "bidirectional"))
    )
    (net (code "45") (name "unconnected-(JP5-SWO{slash}TDO-Pad6)") (class "Default")
      (node (ref "JP5") (pin "6") (pinfunction "SWO/TDO_6") (pintype "bidirectional"))
    )
    (net (code "46") (name "unconnected-(LED1-DO-Pad3)") (class "Default")
      (node (ref "LED1") (pin "3") (pinfunction "DO_3") (pintype "output"))
    )
    (net (code "47") (name "unconnected-(U2-PA18-Pad19)") (class "Default")
      (node (ref "U2") (pin "19") (pinfunction "PA18_19") (pintype "bidirectional"))
    )
    (net (code "48") (name "unconnected-(U2-PA19-Pad20)") (class "Default")
      (node (ref "U2") (pin "20") (pinfunction "PA19_20") (pintype "bidirectional"))
    )
    (net (code "49") (name "unconnected-(U2-PA27-Pad25)") (class "Default")
      (node (ref "U2") (pin "25") (pinfunction "PA27_25") (pintype "bidirectional"))
    )
    (net (code "50") (name "unconnected-(U2-PA28-Pad27)") (class "Default")
      (node (ref "U2") (pin "27") (pinfunction "PA28_27") (pintype "bidirectional"))
    )
    (net (code "51") (name "unconnected-(U4-P4-Pad4)") (class "Default")
      (node (ref "U4") (pin "4") (pinfunction "P4_4") (pintype "bidirectional"))
    )
    (net (code "52") (name "~{RESET}") (class "Default")
      (node (ref "JP5") (pin "10") (pinfunction "NRESET_10") (pintype "bidirectional"))
      (node (ref "R8") (pin "1") (pinfunction "1_1") (pintype "passive"))
      (node (ref "SW1") (pin "1") (pinfunction "P_1") (pintype "passive"))
      (node (ref "SW1") (pin "3") (pinfunction "P1_3") (pintype "passive"))
      (node (ref "U2") (pin "26") (pinfunction "~{RESET}_26") (pintype "input"))
    )
  )
)
